# LEO_COTS_no_ant_rev0.net
KiCad netlist of a schematic drawn in Altium Designer
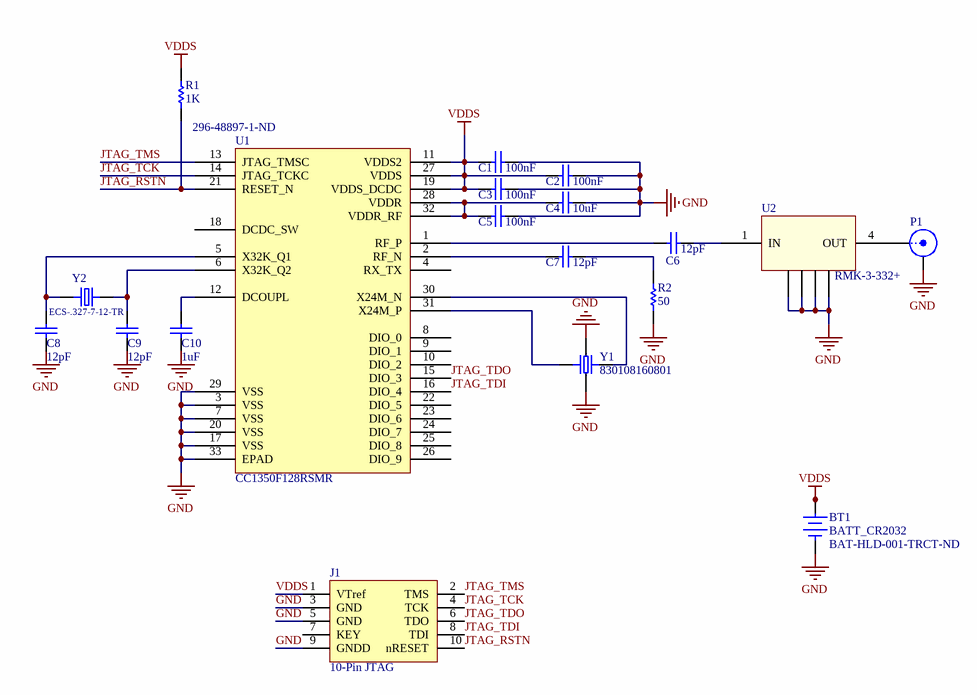
[diagram p0: LEO_COTS_no_ant_rev0.SchDoc]

(export (version "E")
  (design (tool "Eeschema 10.0.6"))
  (components
    (comp (ref "BT1")
      (value "BATT_CR2032")
      (footprint "BAT-HLD-001-TR")
      (description "CR2032 Battery Holder")
      (fields (field (name "SUPPLIER PART NUMBER 1") "BAT-HLD-001-TRCT-ND"))
      (libsource (lib "LEO_COTS_components") (part "BATT_CR2032"))
    )
    (comp (ref "C1")
      (value "100nF")
      (footprint "CAPC0603X04N")
      (description "CAP CER 100nF 0201")
      (fields (field (name "Comment") "CAP_0201"))
      (libsource (lib "LEO_COTS_components") (part "CAP_0201"))
    )
    (comp (ref "C2")
      (value "100nF")
      (footprint "CAPC0603X04N")
      (description "CAP CER 100nF 0201")
      (fields (field (name "Comment") "CAP_0201"))
      (libsource (lib "LEO_COTS_components") (part "CAP_0201"))
    )
    (comp (ref "C3")
      (value "100nF")
      (footprint "CAPC0603X04N")
      (description "CAP CER 100nF 0201")
      (fields (field (name "Comment") "CAP_0201"))
      (libsource (lib "LEO_COTS_components") (part "CAP_0201"))
    )
    (comp (ref "C4")
      (value "10uF")
      (footprint "CAPC1608X05N")
      (description "CAP CER 10uF 0603")
      (fields (field (name "Comment") "CAP_0603"))
      (libsource (lib "LEO_COTS_components") (part "CAP_0603"))
    )
    (comp (ref "C5")
      (value "100nF")
      (footprint "CAPC0603X04N")
      (description "CAP CER 100nF 0201")
      (fields (field (name "Comment") "CAP_0201"))
      (libsource (lib "LEO_COTS_components") (part "CAP_0201"))
    )
    (comp (ref "C6")
      (value "12pF")
      (footprint "1608[0603]")
      (description "CAP CER 12pF 0603")
      (fields (field (name "Comment") "CAP"))
      (libsource (lib "LEO_COTS_components") (part "CAP"))
    )
    (comp (ref "C7")
      (value "12pF")
      (footprint "CAPC0603X04N")
      (description "CAP CER 12pF 0201")
      (fields (field (name "Comment") "CAP_0201"))
      (libsource (lib "LEO_COTS_components") (part "CAP_0201"))
    )
    (comp (ref "C8")
      (value "12pF")
      (footprint "CAPC0603X04N")
      (description "CAP CER 12pF 0201")
      (fields (field (name "Comment") "CAP_0201"))
      (libsource (lib "LEO_COTS_components") (part "CAP_0201"))
    )
    (comp (ref "C9")
      (value "12pF")
      (footprint "CAPC0603X04N")
      (description "CAP CER 12pF 0201")
      (fields (field (name "Comment") "CAP_0201"))
      (libsource (lib "LEO_COTS_components") (part "CAP_0201"))
    )
    (comp (ref "C10")
      (value "1uF")
      (footprint "CAPC0603X04N")
      (description "CAP CER 1uF 0201")
      (fields (field (name "Comment") "CAP_0201"))
      (libsource (lib "LEO_COTS_components") (part "CAP_0201"))
    )
    (comp (ref "J1")
      (value "10-Pin JTAG")
      (footprint "FTSH-105-01-F-DV-007-K")
      (description "10-pin JTAG")
      (libsource (lib "LEO_COTS_components") (part "CM10"))
    )
    (comp (ref "P1")
      (value "1909763-1")
      (footprint "1909763-1")
      (description "CONN UMCC JACK STR 50OHM SMD")
      (libsource (lib "LEO_COTS_components") (part "1909763-1"))
    )
    (comp (ref "R1")
      (value "1K")
      (footprint "CAPC0603X04N")
      (description "RES 1K OHM 0201")
      (fields (field (name "Comment") "RES_0201") (field (name "PUBLISHER") "Altium Limited"))
      (libsource (lib "LEO_COTS_components") (part "Res Semi"))
    )
    (comp (ref "R2")
      (value "50")
      (footprint "CAPC0603X04N")
      (description "RES 50 OHM 0201")
      (fields (field (name "Comment") "RES_0201") (field (name "PUBLISHER") "Altium Limited"))
      (libsource (lib "LEO_COTS_components") (part "Res Semi"))
    )
    (comp (ref "U1")
      (value "CC1350F128RSMR")
      (footprint "QFN40P400X400X100-33N")
      (description "Ultra-Low-Power Dual-Band Wireless MCU")
      (fields (field (name "SUPPLIER PART NUMBER 1") "296-48897-1-ND"))
      (libsource (lib "LEO_COTS_components") (part "CC1350F128RSMR"))
    )
    (comp (ref "U2")
      (value "RMK-3-332+")
      (footprint "RMK-3-331+")
      (description "3x Frequency Multiplier")
      (libsource (lib "LEO_COTS_components") (part "RMK-3-332+"))
    )
    (comp (ref "Y1")
      (value "830108160801")
      (footprint "LFXTAL081608")
      (description "24 MHz crystal")
      (fields (field (name "MP") "ECS-.327-7-12-TR"))
      (libsource (lib "LEO_COTS_components") (part "830108160801"))
    )
    (comp (ref "Y2")
      (value "ECS-.327-7-12-TR")
      (footprint "XTAL_ECS-.327-7-12-TR")
      (description "32.768 kHz SMD Crystal")
      (libsource (lib "LEO_COTS_components") (part "ECS-.327-7-12-TR"))
    )
  )
  (nets
    (net (code "1") (name "/JTAG_RSTN") (class "Default")
      (node (ref "J1") (pin "10") (pinfunction "nRESET_10") (pintype "passive"))
      (node (ref "R1") (pin "1") (pinfunction "1_1") (pintype "passive"))
      (node (ref "U1") (pin "21") (pinfunction "RESET_N_21") (pintype "passive"))
    )
    (net (code "2") (name "/JTAG_TCK") (class "Default")
      (node (ref "J1") (pin "4") (pinfunction "TCK_4") (pintype "passive"))
      (node (ref "U1") (pin "14") (pinfunction "JTAG_TCKC_14") (pintype "passive"))
    )
    (net (code "3") (name "/JTAG_TDI") (class "Default")
      (node (ref "J1") (pin "8") (pinfunction "TDI_8") (pintype "passive"))
      (node (ref "U1") (pin "16") (pinfunction "DIO_4_16") (pintype "passive"))
    )
    (net (code "4") (name "/JTAG_TDO") (class "Default")
      (node (ref "J1") (pin "6") (pinfunction "TDO_6") (pintype "passive"))
      (node (ref "U1") (pin "15") (pinfunction "DIO_3_15") (pintype "passive"))
    )
    (net (code "5") (name "/JTAG_TMS") (class "Default")
      (node (ref "J1") (pin "2") (pinfunction "TMS_2") (pintype "passive"))
      (node (ref "U1") (pin "13") (pinfunction "JTAG_TMSC_13") (pintype "passive"))
    )
    (net (code "6") (name "GND") (class "Default")
      (node (ref "BT1") (pin "N1") (pinfunction "-_N1") (pintype "passive"))
      (node (ref "C1") (pin "1") (pinfunction "1_1") (pintype "passive"))
      (node (ref "C10") (pin "1") (pinfunction "1_1") (pintype "passive"))
      (node (ref "C2") (pin "1") (pinfunction "1_1") (pintype "passive"))
      (node (ref "C3") (pin "1") (pinfunction "1_1") (pintype "passive"))
      (node (ref "C4") (pin "2") (pinfunction "2_2") (pintype "passive"))
      (node (ref "C5") (pin "1") (pinfunction "1_1") (pintype "passive"))
      (node (ref "C8") (pin "1") (pinfunction "1_1") (pintype "passive"))
      (node (ref "C9") (pin "1") (pinfunction "1_1") (pintype "passive"))
      (node (ref "J1") (pin "3") (pinfunction "GND_3") (pintype "passive"))
      (node (ref "J1") (pin "5") (pinfunction "GND_5") (pintype "passive"))
      (node (ref "J1") (pin "9") (pinfunction "GNDD_9") (pintype "passive"))
      (node (ref "P1") (pin "2") (pinfunction "Y_2") (pintype "passive"))
      (node (ref "R2") (pin "1") (pinfunction "1_1") (pintype "passive"))
      (node (ref "U1") (pin "17") (pinfunction "VSS_17") (pintype "passive"))
      (node (ref "U1") (pin "20") (pinfunction "VSS_20") (pintype "passive"))
      (node (ref "U1") (pin "29") (pinfunction "VSS_29") (pintype "passive"))
      (node (ref "U1") (pin "3") (pinfunction "VSS_3") (pintype "passive"))
      (node (ref "U1") (pin "33") (pinfunction "EPAD_33") (pintype "passive"))
      (node (ref "U1") (pin "7") (pinfunction "VSS_7") (pintype "passive"))
      (node (ref "U2") (pin "2") (pinfunction "2_2") (pintype "passive"))
      (node (ref "U2") (pin "3") (pinfunction "3_3") (pintype "passive"))
      (node (ref "U2") (pin "5") (pinfunction "5_5") (pintype "passive"))
      (node (ref "U2") (pin "6") (pinfunction "6_6") (pintype "passive"))
      (node (ref "Y1") (pin "2") (pinfunction "2_2") (pintype "passive"))
      (node (ref "Y1") (pin "4") (pinfunction "4_4") (pintype "passive"))
    )
    (net (code "7") (name "Net-(C7-Pad1)") (class "Default")
      (node (ref "C7") (pin "1") (pinfunction "1_1") (pintype "passive"))
      (node (ref "R2") (pin "2") (pinfunction "2_2") (pintype "passive"))
    )
    (net (code "8") (name "Net-(P1-X)") (class "Default")
      (node (ref "P1") (pin "1") (pinfunction "X_1") (pintype "passive"))
      (node (ref "U2") (pin "4") (pinfunction "OUT_4") (pintype "passive"))
    )
    (net (code "9") (name "Net-(U1-DCOUPL)") (class "Default")
      (node (ref "C10") (pin "2") (pinfunction "2_2") (pintype "passive"))
      (node (ref "U1") (pin "12") (pinfunction "DCOUPL_12") (pintype "passive"))
    )
    (net (code "10") (name "Net-(U1-RF_N)") (class "Default")
      (node (ref "C7") (pin "2") (pinfunction "2_2") (pintype "passive"))
      (node (ref "U1") (pin "2") (pinfunction "RF_N_2") (pintype "passive"))
    )
    (net (code "11") (name "Net-(U1-RF_P)") (class "Default")
      (node (ref "C6") (pin "1") (pinfunction "1_1") (pintype "passive"))
      (node (ref "U1") (pin "1") (pinfunction "RF_P_1") (pintype "passive"))
    )
    (net (code "12") (name "Net-(U1-VDDR)") (class "Default")
      (node (ref "C4") (pin "1") (pinfunction "1_1") (pintype "passive"))
      (node (ref "C5") (pin "2") (pinfunction "2_2") (pintype "passive"))
      (node (ref "U1") (pin "28") (pinfunction "VDDR_28") (pintype "passive"))
      (node (ref "U1") (pin "32") (pinfunction "VDDR_RF_32") (pintype "passive"))
    )
    (net (code "13") (name "Net-(U1-X24M_N)") (class "Default")
      (node (ref "U1") (pin "30") (pinfunction "X24M_N_30") (pintype "passive"))
      (node (ref "Y1") (pin "3") (pinfunction "3_3") (pintype "passive"))
    )
    (net (code "14") (name "Net-(U1-X24M_P)") (class "Default")
      (node (ref "U1") (pin "31") (pinfunction "X24M_P_31") (pintype "passive"))
      (node (ref "Y1") (pin "1") (pinfunction "1_1") (pintype "passive"))
    )
    (net (code "15") (name "Net-(U1-X32K_Q1)") (class "Default")
      (node (ref "C8") (pin "2") (pinfunction "2_2") (pintype "passive"))
      (node (ref "U1") (pin "5") (pinfunction "X32K_Q1_5") (pintype "passive"))
      (node (ref "Y2") (pin "1") (pinfunction "1_1") (pintype "passive"))
    )
    (net (code "16") (name "Net-(U1-X32K_Q2)") (class "Default")
      (node (ref "C9") (pin "2") (pinfunction "2_2") (pintype "passive"))
      (node (ref "U1") (pin "6") (pinfunction "X32K_Q2_6") (pintype "passive"))
      (node (ref "Y2") (pin "2") (pinfunction "2_2") (pintype "passive"))
    )
    (net (code "17") (name "Net-(U2-IN)") (class "Default")
      (node (ref "C6") (pin "2") (pinfunction "2_2") (pintype "passive"))
      (node (ref "U2") (pin "1") (pinfunction "IN_1") (pintype "passive"))
    )
    (net (code "18") (name "VDDS") (class "Default")
      (node (ref "BT1") (pin "P1") (pinfunction "+_P1") (pintype "passive"))
      (node (ref "BT1") (pin "P2") (pinfunction "+_P2") (pintype "passive"))
      (node (ref "C1") (pin "2") (pinfunction "2_2") (pintype "passive"))
      (node (ref "C2") (pin "2") (pinfunction "2_2") (pintype "passive"))
      (node (ref "C3") (pin "2") (pinfunction "2_2") (pintype "passive"))
      (node (ref "J1") (pin "1") (pinfunction "VTref_1") (pintype "passive"))
      (node (ref "R1") (pin "2") (pinfunction "2_2") (pintype "passive"))
      (node (ref "U1") (pin "11") (pinfunction "VDDS2_11") (pintype "passive"))
      (node (ref "U1") (pin "19") (pinfunction "VDDS_DCDC_19") (pintype "passive"))
      (node (ref "U1") (pin "27") (pinfunction "VDDS_27") (pintype "passive"))
    )
    (net (code "19") (name "unconnected-(J1-KEY-Pad7)") (class "Default")
      (node (ref "J1") (pin "7") (pinfunction "KEY_7") (pintype "passive"))
    )
    (net (code "20") (name "unconnected-(U1-DCDC_SW-Pad18)") (class "Default")
      (node (ref "U1") (pin "18") (pinfunction "DCDC_SW_18") (pintype "passive"))
    )
    (net (code "21") (name "unconnected-(U1-DIO_0-Pad8)") (class "Default")
      (node (ref "U1") (pin "8") (pinfunction "DIO_0_8") (pintype "passive"))
    )
    (net (code "22") (name "unconnected-(U1-DIO_1-Pad9)") (class "Default")
      (node (ref "U1") (pin "9") (pinfunction "DIO_1_9") (pintype "passive"))
    )
    (net (code "23") (name "unconnected-(U1-DIO_2-Pad10)") (class "Default")
      (node (ref "U1") (pin "10") (pinfunction "DIO_2_10") (pintype "passive"))
    )
    (net (code "24") (name "unconnected-(U1-DIO_5-Pad22)") (class "Default")
      (node (ref "U1") (pin "22") (pinfunction "DIO_5_22") (pintype "passive"))
    )
    (net (code "25") (name "unconnected-(U1-DIO_6-Pad23)") (class "Default")
      (node (ref "U1") (pin "23") (pinfunction "DIO_6_23") (pintype "passive"))
    )
    (net (code "26") (name "unconnected-(U1-DIO_7-Pad24)") (class "Default")
      (node (ref "U1") (pin "24") (pinfunction "DIO_7_24") (pintype "passive"))
    )
    (net (code "27") (name "unconnected-(U1-DIO_8-Pad25)") (class "Default")
      (node (ref "U1") (pin "25") (pinfunction "DIO_8_25") (pintype "passive"))
    )
    (net (code "28") (name "unconnected-(U1-DIO_9-Pad26)") (class "Default")
      (node (ref "U1") (pin "26") (pinfunction "DIO_9_26") (pintype "passive"))
    )
    (net (code "29") (name "unconnected-(U1-RX_TX-Pad4)") (class "Default")
      (node (ref "U1") (pin "4") (pinfunction "RX_TX_4") (pintype "passive"))
    )
  )
)
